# Victor_9000_DiskOnChip_v2.net
KiCad netlist of a schematic drawn in EAGLE
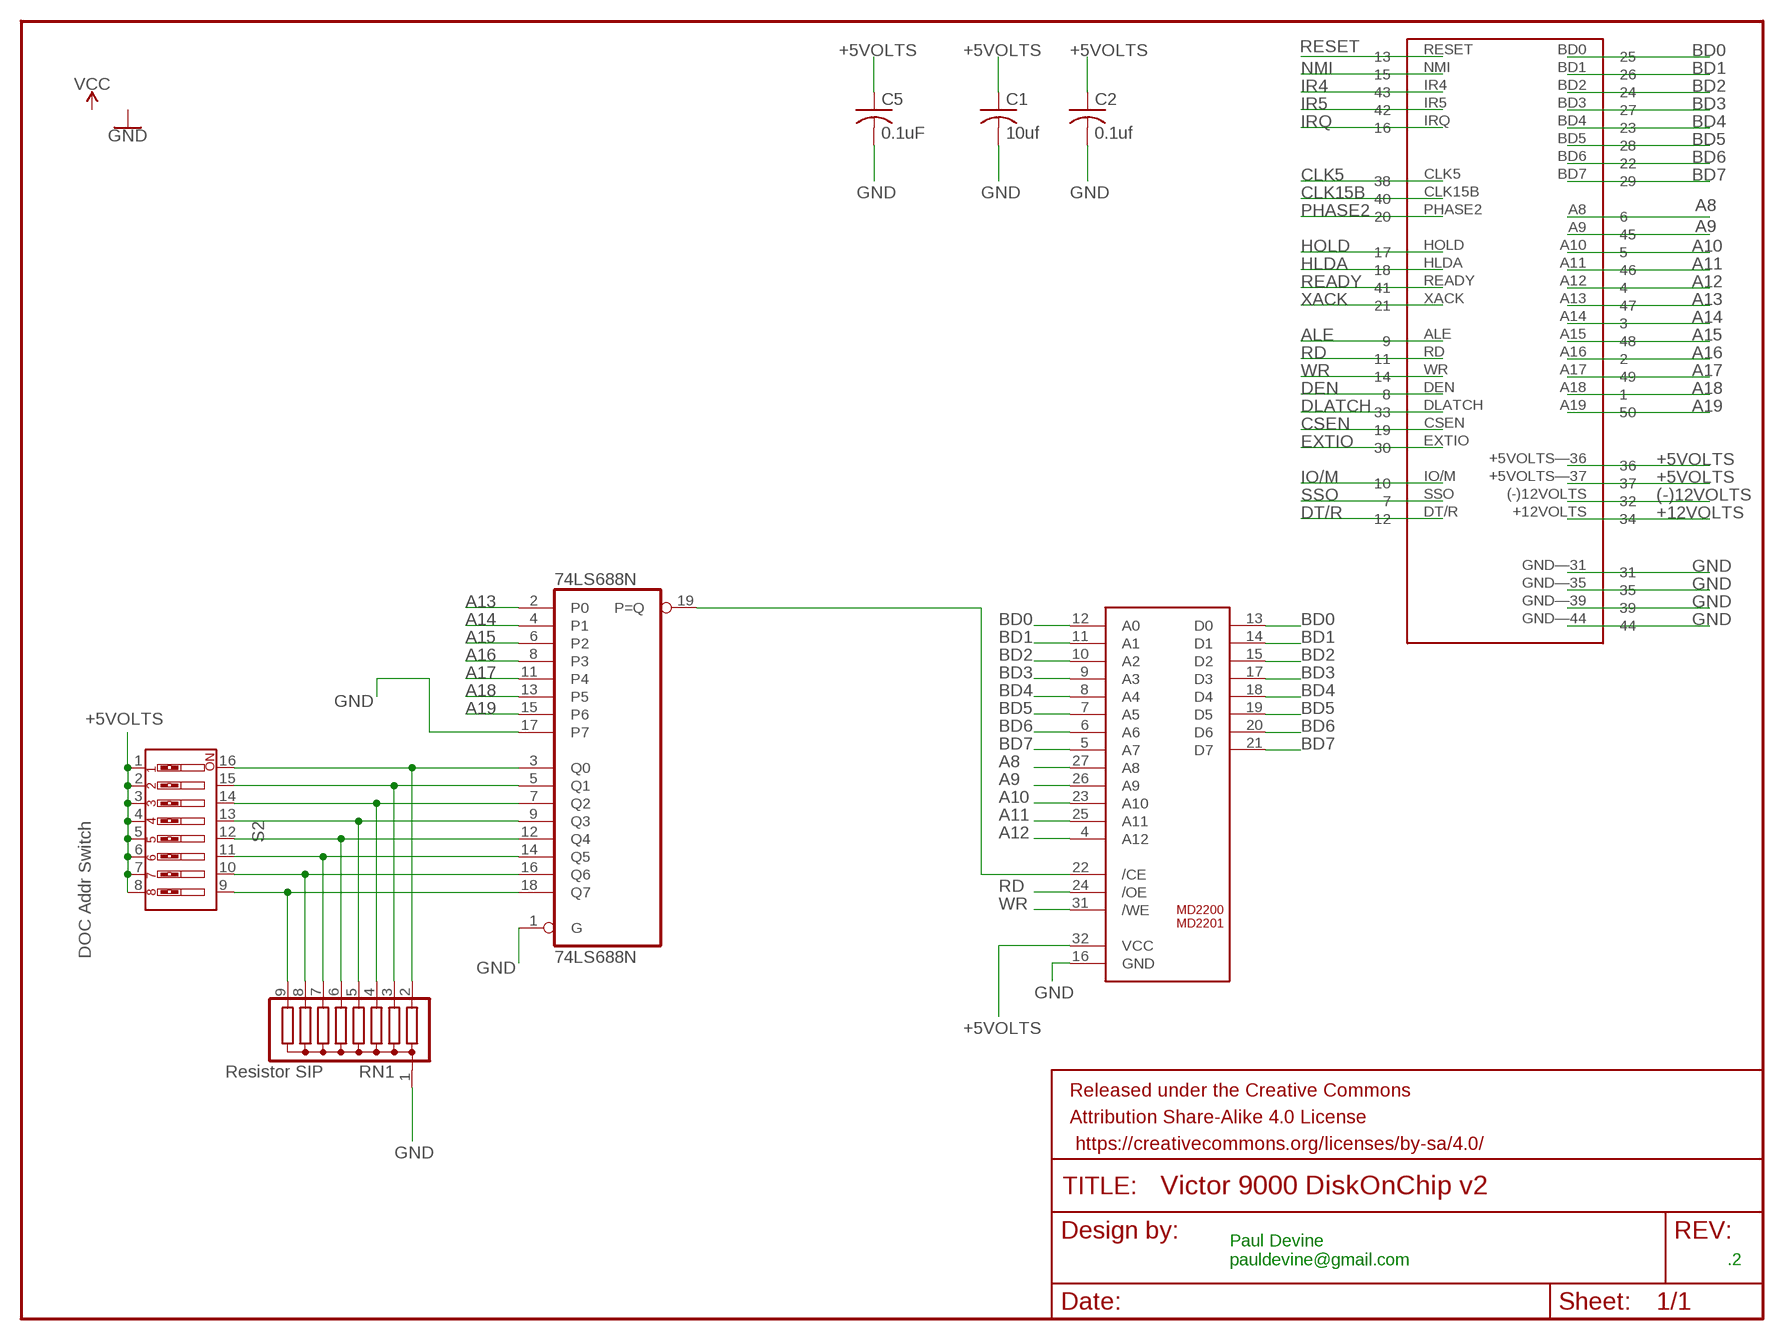
[diagram p0: schematic, sheet 1]

(export (version "E")
  (design (tool "Eeschema 10.0.6"))
  (components
    (comp (ref "74LS688N")
      (value "74LS688N")
      (footprint "eagle-import:DIL20")
      (libsource (lib "eagle-import") (part "74688NLS"))
    )
    (comp (ref "C1")
      (value "10uf")
      (footprint "eagle-import:C025-050X050")
      (libsource (lib "eagle-import") (part "C-US025-050X050"))
    )
    (comp (ref "C2")
      (value "0.1uf")
      (footprint "eagle-import:C025-050X050")
      (libsource (lib "eagle-import") (part "C-US025-050X050"))
    )
    (comp (ref "C5")
      (value "0.1uF")
      (footprint "eagle-import:C025-050X050")
      (libsource (lib "eagle-import") (part "C-US025-050X050"))
    )
    (comp (ref "DISKONCHIP2000")
      (value "DOC2000")
      (footprint "eagle-import:DIL32")
      (libsource (lib "eagle-import") (part "DOC2000"))
    )
    (comp (ref "FRAME1")
      (value "FRAME-LETTER")
      (footprint "eagle-import:CREATIVE_COMMONS")
      (libsource (lib "eagle-import") (part "FRAME-LETTER"))
    )
    (comp (ref "RN1")
      (value "Resistor SIP")
      (footprint "eagle-import:SIL9")
      (libsource (lib "eagle-import") (part "G08R"))
    )
    (comp (ref "S2")
      (value "DOC Addr Switch")
      (footprint "eagle-import:DIPSWITCH-08")
      (libsource (lib "eagle-import") (part "DIP-08-PTH"))
    )
    (comp (ref "U$1")
      (value "VICTOR_GOLD_FINGERS")
      (footprint "eagle-import:VICTOR_GOLD_FINGERS")
      (libsource (lib "eagle-import") (part "VICTOR_GOLD_FINGERS"))
    )
  )
  (nets
    (net (code "1") (name "/(-)12VOLTS") (class "Default")
      (node (ref "U$1") (pin "(-)12VOLTS") (pinfunction "32_(-)12VOLTS") (pintype "power_in"))
    )
    (net (code "2") (name "/+5VOLTS") (class "Default")
      (node (ref "C1") (pin "1") (pinfunction "1_1") (pintype "passive"))
      (node (ref "C2") (pin "1") (pinfunction "1_1") (pintype "passive"))
      (node (ref "C5") (pin "1") (pinfunction "1_1") (pintype "passive"))
      (node (ref "DISKONCHIP2000") (pin "32") (pinfunction "VCC_32") (pintype "power_in"))
      (node (ref "S2") (pin "1") (pinfunction "1_1") (pintype "passive"))
      (node (ref "S2") (pin "2") (pinfunction "2_2") (pintype "passive"))
      (node (ref "S2") (pin "3") (pinfunction "3_3") (pintype "passive"))
      (node (ref "S2") (pin "4") (pinfunction "4_4") (pintype "passive"))
      (node (ref "S2") (pin "5") (pinfunction "5_5") (pintype "passive"))
      (node (ref "S2") (pin "6") (pinfunction "6_6") (pintype "passive"))
      (node (ref "S2") (pin "7") (pinfunction "7_7") (pintype "passive"))
      (node (ref "S2") (pin "8") (pinfunction "8_8") (pintype "passive"))
      (node (ref "U$1") (pin "+5VOLTS—36") (pinfunction "36_+5VOLTS—36") (pintype "power_in"))
      (node (ref "U$1") (pin "+5VOLTS—37") (pinfunction "37_+5VOLTS—37") (pintype "power_in"))
    )
    (net (code "3") (name "/+12VOLTS") (class "Default")
      (node (ref "U$1") (pin "+12VOLTS") (pinfunction "34_+12VOLTS") (pintype "power_in"))
    )
    (net (code "4") (name "/A8") (class "Default")
      (node (ref "DISKONCHIP2000") (pin "27") (pinfunction "A8_27") (pintype "bidirectional"))
      (node (ref "U$1") (pin "A8") (pinfunction "6_A8") (pintype "bidirectional"))
    )
    (net (code "5") (name "/A9") (class "Default")
      (node (ref "DISKONCHIP2000") (pin "26") (pinfunction "A9_26") (pintype "bidirectional"))
      (node (ref "U$1") (pin "A9") (pinfunction "45_A9") (pintype "bidirectional"))
    )
    (net (code "6") (name "/A10") (class "Default")
      (node (ref "DISKONCHIP2000") (pin "23") (pinfunction "A10_23") (pintype "bidirectional"))
      (node (ref "U$1") (pin "A10") (pinfunction "5_A10") (pintype "bidirectional"))
    )
    (net (code "7") (name "/A11") (class "Default")
      (node (ref "DISKONCHIP2000") (pin "25") (pinfunction "A11_25") (pintype "bidirectional"))
      (node (ref "U$1") (pin "A11") (pinfunction "46_A11") (pintype "bidirectional"))
    )
    (net (code "8") (name "/A12") (class "Default")
      (node (ref "DISKONCHIP2000") (pin "4") (pinfunction "A12_4") (pintype "bidirectional"))
      (node (ref "U$1") (pin "A12") (pinfunction "4_A12") (pintype "bidirectional"))
    )
    (net (code "9") (name "/A13") (class "Default")
      (node (ref "74LS688N") (pin "2") (pinfunction "P0_2") (pintype "input"))
      (node (ref "U$1") (pin "A13") (pinfunction "47_A13") (pintype "bidirectional"))
    )
    (net (code "10") (name "/A14") (class "Default")
      (node (ref "74LS688N") (pin "4") (pinfunction "P1_4") (pintype "input"))
      (node (ref "U$1") (pin "A14") (pinfunction "3_A14") (pintype "bidirectional"))
    )
    (net (code "11") (name "/A15") (class "Default")
      (node (ref "74LS688N") (pin "6") (pinfunction "P2_6") (pintype "input"))
      (node (ref "U$1") (pin "A15") (pinfunction "48_A15") (pintype "bidirectional"))
    )
    (net (code "12") (name "/A16") (class "Default")
      (node (ref "74LS688N") (pin "8") (pinfunction "P3_8") (pintype "input"))
      (node (ref "U$1") (pin "A16") (pinfunction "2_A16") (pintype "bidirectional"))
    )
    (net (code "13") (name "/A17") (class "Default")
      (node (ref "74LS688N") (pin "11") (pinfunction "P4_11") (pintype "input"))
      (node (ref "U$1") (pin "A17") (pinfunction "49_A17") (pintype "bidirectional"))
    )
    (net (code "14") (name "/A18") (class "Default")
      (node (ref "74LS688N") (pin "13") (pinfunction "P5_13") (pintype "input"))
      (node (ref "U$1") (pin "A18") (pinfunction "1_A18") (pintype "bidirectional"))
    )
    (net (code "15") (name "/A19") (class "Default")
      (node (ref "74LS688N") (pin "15") (pinfunction "P6_15") (pintype "input"))
      (node (ref "U$1") (pin "A19") (pinfunction "50_A19") (pintype "bidirectional"))
    )
    (net (code "16") (name "/ALE") (class "Default")
      (node (ref "U$1") (pin "ALE") (pinfunction "9_ALE") (pintype "bidirectional"))
    )
    (net (code "17") (name "/BD0") (class "Default")
      (node (ref "DISKONCHIP2000") (pin "12") (pinfunction "A0_12") (pintype "bidirectional"))
      (node (ref "DISKONCHIP2000") (pin "13") (pinfunction "D0_13") (pintype "bidirectional"))
      (node (ref "U$1") (pin "BD0") (pinfunction "25_BD0") (pintype "bidirectional"))
    )
    (net (code "18") (name "/BD1") (class "Default")
      (node (ref "DISKONCHIP2000") (pin "11") (pinfunction "A1_11") (pintype "bidirectional"))
      (node (ref "DISKONCHIP2000") (pin "14") (pinfunction "D1_14") (pintype "bidirectional"))
      (node (ref "U$1") (pin "BD1") (pinfunction "26_BD1") (pintype "bidirectional"))
    )
    (net (code "19") (name "/BD2") (class "Default")
      (node (ref "DISKONCHIP2000") (pin "10") (pinfunction "A2_10") (pintype "bidirectional"))
      (node (ref "DISKONCHIP2000") (pin "15") (pinfunction "D2_15") (pintype "bidirectional"))
      (node (ref "U$1") (pin "BD2") (pinfunction "24_BD2") (pintype "bidirectional"))
    )
    (net (code "20") (name "/BD3") (class "Default")
      (node (ref "DISKONCHIP2000") (pin "17") (pinfunction "D3_17") (pintype "bidirectional"))
      (node (ref "DISKONCHIP2000") (pin "9") (pinfunction "A3_9") (pintype "bidirectional"))
      (node (ref "U$1") (pin "BD3") (pinfunction "27_BD3") (pintype "bidirectional"))
    )
    (net (code "21") (name "/BD4") (class "Default")
      (node (ref "DISKONCHIP2000") (pin "18") (pinfunction "D4_18") (pintype "bidirectional"))
      (node (ref "DISKONCHIP2000") (pin "8") (pinfunction "A4_8") (pintype "bidirectional"))
      (node (ref "U$1") (pin "BD4") (pinfunction "23_BD4") (pintype "bidirectional"))
    )
    (net (code "22") (name "/BD5") (class "Default")
      (node (ref "DISKONCHIP2000") (pin "19") (pinfunction "D5_19") (pintype "bidirectional"))
      (node (ref "DISKONCHIP2000") (pin "7") (pinfunction "A5_7") (pintype "bidirectional"))
      (node (ref "U$1") (pin "BD5") (pinfunction "28_BD5") (pintype "bidirectional"))
    )
    (net (code "23") (name "/BD6") (class "Default")
      (node (ref "DISKONCHIP2000") (pin "20") (pinfunction "D6_20") (pintype "bidirectional"))
      (node (ref "DISKONCHIP2000") (pin "6") (pinfunction "A6_6") (pintype "bidirectional"))
      (node (ref "U$1") (pin "BD6") (pinfunction "22_BD6") (pintype "bidirectional"))
    )
    (net (code "24") (name "/BD7") (class "Default")
      (node (ref "DISKONCHIP2000") (pin "21") (pinfunction "D7_21") (pintype "bidirectional"))
      (node (ref "DISKONCHIP2000") (pin "5") (pinfunction "A7_5") (pintype "bidirectional"))
      (node (ref "U$1") (pin "BD7") (pinfunction "29_BD7") (pintype "bidirectional"))
    )
    (net (code "25") (name "/CLK5") (class "Default")
      (node (ref "U$1") (pin "CLK5") (pinfunction "38_CLK5") (pintype "bidirectional"))
    )
    (net (code "26") (name "/CLK15B") (class "Default")
      (node (ref "U$1") (pin "CLK15B") (pinfunction "40_CLK15B") (pintype "bidirectional"))
    )
    (net (code "27") (name "/CSEN") (class "Default")
      (node (ref "U$1") (pin "CSEN") (pinfunction "19_CSEN") (pintype "bidirectional"))
    )
    (net (code "28") (name "/DEN") (class "Default")
      (node (ref "U$1") (pin "DEN") (pinfunction "8_DEN") (pintype "bidirectional"))
    )
    (net (code "29") (name "/DLATCH") (class "Default")
      (node (ref "U$1") (pin "DLATCH") (pinfunction "33_DLATCH") (pintype "bidirectional"))
    )
    (net (code "30") (name "/DT{slash}R") (class "Default")
      (node (ref "U$1") (pin "DT/R") (pinfunction "12_DT/R") (pintype "bidirectional"))
    )
    (net (code "31") (name "/EXTIO") (class "Default")
      (node (ref "U$1") (pin "EXTIO") (pinfunction "30_EXTIO") (pintype "bidirectional"))
    )
    (net (code "32") (name "/HLDA") (class "Default")
      (node (ref "U$1") (pin "HLDA") (pinfunction "18_HLDA") (pintype "bidirectional"))
    )
    (net (code "33") (name "/HOLD") (class "Default")
      (node (ref "U$1") (pin "HOLD") (pinfunction "17_HOLD") (pintype "bidirectional"))
    )
    (net (code "34") (name "/IO{slash}M") (class "Default")
      (node (ref "U$1") (pin "IO/M") (pinfunction "10_IO/M") (pintype "bidirectional"))
    )
    (net (code "35") (name "/IR4") (class "Default")
      (node (ref "U$1") (pin "IR4") (pinfunction "43_IR4") (pintype "bidirectional"))
    )
    (net (code "36") (name "/IR5") (class "Default")
      (node (ref "U$1") (pin "IR5") (pinfunction "42_IR5") (pintype "bidirectional"))
    )
    (net (code "37") (name "/IRQ") (class "Default")
      (node (ref "U$1") (pin "IRQ") (pinfunction "16_IRQ") (pintype "bidirectional"))
    )
    (net (code "38") (name "/NMI") (class "Default")
      (node (ref "U$1") (pin "NMI") (pinfunction "15_NMI") (pintype "bidirectional"))
    )
    (net (code "39") (name "/PHASE2") (class "Default")
      (node (ref "U$1") (pin "PHASE2") (pinfunction "20_PHASE2") (pintype "bidirectional"))
    )
    (net (code "40") (name "/RD") (class "Default")
      (node (ref "DISKONCHIP2000") (pin "24") (pinfunction "/OE_24") (pintype "input"))
      (node (ref "U$1") (pin "RD") (pinfunction "11_RD") (pintype "bidirectional"))
    )
    (net (code "41") (name "/READY") (class "Default")
      (node (ref "U$1") (pin "READY") (pinfunction "41_READY") (pintype "bidirectional"))
    )
    (net (code "42") (name "/RESET") (class "Default")
      (node (ref "U$1") (pin "RESET") (pinfunction "13_RESET") (pintype "bidirectional"))
    )
    (net (code "43") (name "/SSO") (class "Default")
      (node (ref "U$1") (pin "SSO") (pinfunction "7_SSO") (pintype "bidirectional"))
    )
    (net (code "44") (name "/WR") (class "Default")
      (node (ref "DISKONCHIP2000") (pin "31") (pinfunction "/WE_31") (pintype "input"))
      (node (ref "U$1") (pin "WR") (pinfunction "14_WR") (pintype "bidirectional"))
    )
    (net (code "45") (name "/XACK") (class "Default")
      (node (ref "U$1") (pin "XACK") (pinfunction "21_XACK") (pintype "bidirectional"))
    )
    (net (code "46") (name "GND") (class "Default")
      (node (ref "74LS688N") (pin "1") (pinfunction "G_1") (pintype "input"))
      (node (ref "74LS688N") (pin "17") (pinfunction "P7_17") (pintype "input"))
      (node (ref "C1") (pin "2") (pinfunction "2_2") (pintype "passive"))
      (node (ref "C2") (pin "2") (pinfunction "2_2") (pintype "passive"))
      (node (ref "C5") (pin "2") (pinfunction "2_2") (pintype "passive"))
      (node (ref "DISKONCHIP2000") (pin "16") (pinfunction "GND_16") (pintype "passive"))
      (node (ref "RN1") (pin "1") (pinfunction "1_1") (pintype "passive"))
      (node (ref "U$1") (pin "GND—31") (pinfunction "31_GND—31") (pintype "power_in"))
      (node (ref "U$1") (pin "GND—35") (pinfunction "35_GND—35") (pintype "power_in"))
      (node (ref "U$1") (pin "GND—39") (pinfunction "39_GND—39") (pintype "power_in"))
      (node (ref "U$1") (pin "GND—44") (pinfunction "44_GND—44") (pintype "power_in"))
    )
    (net (code "47") (name "Net-(74LS688NA-P=Q)") (class "Default")
      (node (ref "74LS688N") (pin "19") (pinfunction "P=Q_19") (pintype "output"))
      (node (ref "DISKONCHIP2000") (pin "22") (pinfunction "/CE_22") (pintype "input"))
    )
    (net (code "48") (name "Net-(74LS688NA-Q0)") (class "Default")
      (node (ref "74LS688N") (pin "3") (pinfunction "Q0_3") (pintype "input"))
      (node (ref "RN1") (pin "2") (pinfunction "2_2") (pintype "passive"))
      (node (ref "S2") (pin "16") (pinfunction "16_16") (pintype "passive"))
    )
    (net (code "49") (name "Net-(74LS688NA-Q1)") (class "Default")
      (node (ref "74LS688N") (pin "5") (pinfunction "Q1_5") (pintype "input"))
      (node (ref "RN1") (pin "3") (pinfunction "3_3") (pintype "passive"))
      (node (ref "S2") (pin "15") (pinfunction "15_15") (pintype "passive"))
    )
    (net (code "50") (name "Net-(74LS688NA-Q2)") (class "Default")
      (node (ref "74LS688N") (pin "7") (pinfunction "Q2_7") (pintype "input"))
      (node (ref "RN1") (pin "4") (pinfunction "4_4") (pintype "passive"))
      (node (ref "S2") (pin "14") (pinfunction "14_14") (pintype "passive"))
    )
    (net (code "51") (name "Net-(74LS688NA-Q3)") (class "Default")
      (node (ref "74LS688N") (pin "9") (pinfunction "Q3_9") (pintype "input"))
      (node (ref "RN1") (pin "5") (pinfunction "5_5") (pintype "passive"))
      (node (ref "S2") (pin "13") (pinfunction "13_13") (pintype "passive"))
    )
    (net (code "52") (name "Net-(74LS688NA-Q4)") (class "Default")
      (node (ref "74LS688N") (pin "12") (pinfunction "Q4_12") (pintype "input"))
      (node (ref "RN1") (pin "6") (pinfunction "6_6") (pintype "passive"))
      (node (ref "S2") (pin "12") (pinfunction "12_12") (pintype "passive"))
    )
    (net (code "53") (name "Net-(74LS688NA-Q5)") (class "Default")
      (node (ref "74LS688N") (pin "14") (pinfunction "Q5_14") (pintype "input"))
      (node (ref "RN1") (pin "7") (pinfunction "7_7") (pintype "passive"))
      (node (ref "S2") (pin "11") (pinfunction "11_11") (pintype "passive"))
    )
    (net (code "54") (name "Net-(74LS688NA-Q6)") (class "Default")
      (node (ref "74LS688N") (pin "16") (pinfunction "Q6_16") (pintype "input"))
      (node (ref "RN1") (pin "8") (pinfunction "8_8") (pintype "passive"))
      (node (ref "S2") (pin "10") (pinfunction "10_10") (pintype "passive"))
    )
    (net (code "55") (name "Net-(74LS688NA-Q7)") (class "Default")
      (node (ref "74LS688N") (pin "18") (pinfunction "Q7_18") (pintype "input"))
      (node (ref "RN1") (pin "9") (pinfunction "9_9") (pintype "passive"))
      (node (ref "S2") (pin "9") (pinfunction "9_9") (pintype "passive"))
    )
  )
)
